# MPU6050.net
KiCad netlist of a schematic drawn in Altium Designer
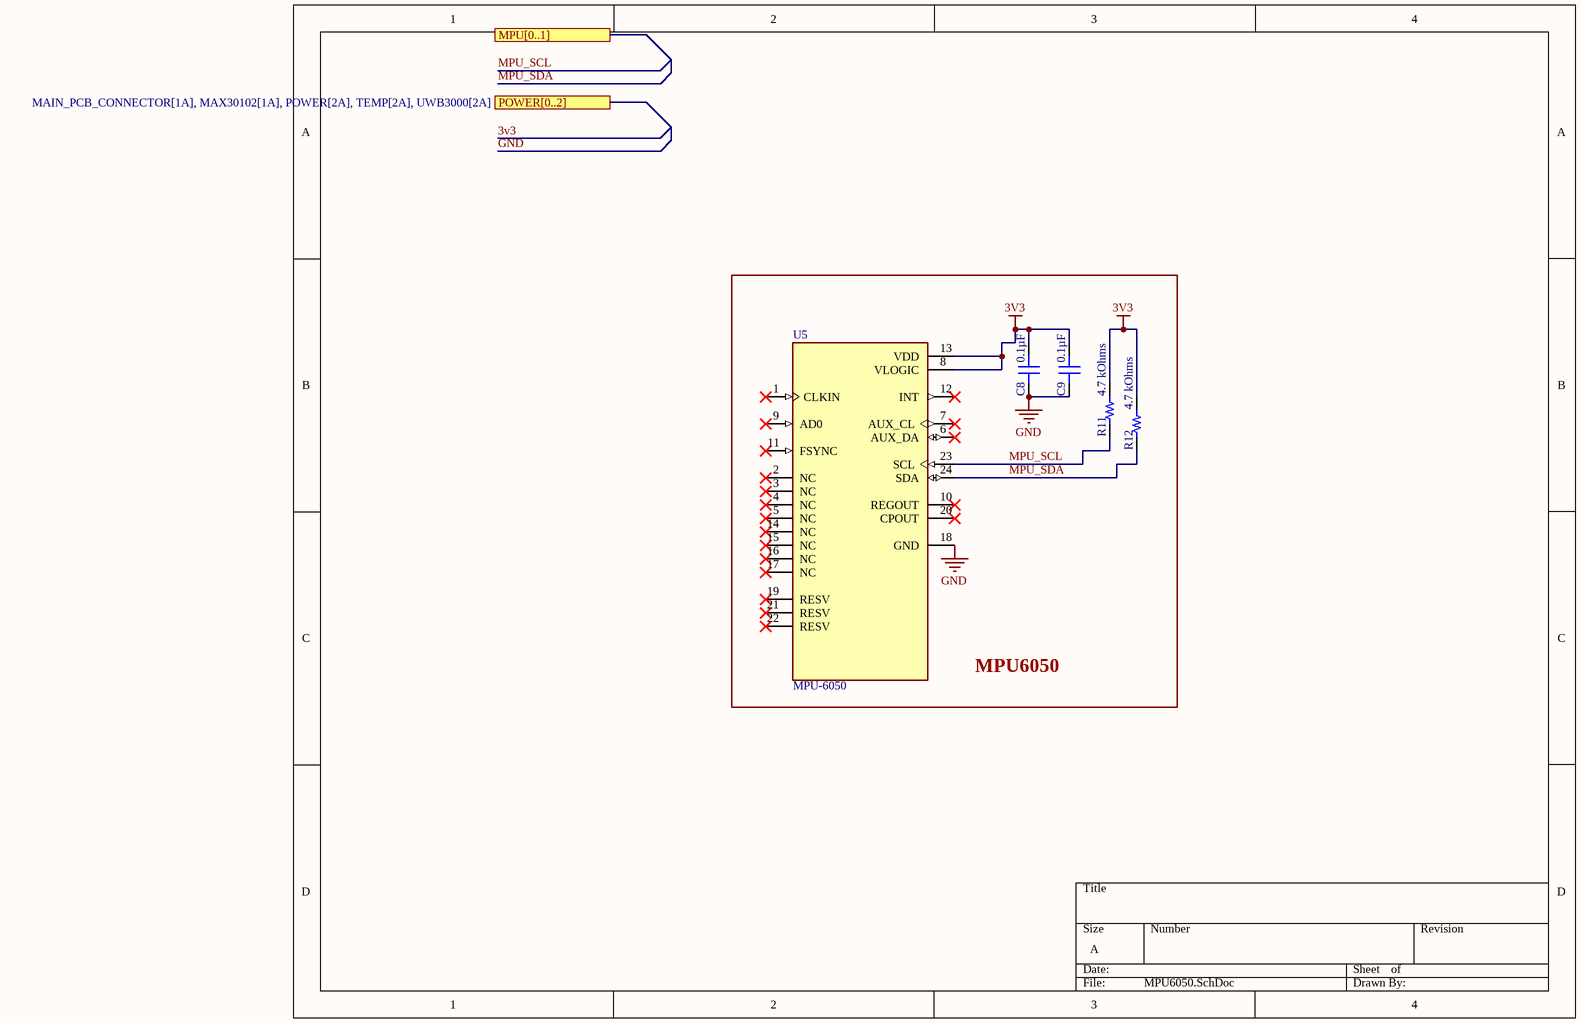
[diagram p0: MPU6050.SchDoc]

(export (version "E")
  (design (tool "Eeschema 10.0.6"))
  (components
    (comp (ref "C8")
      (value "0.1µF")
      (footprint "CAP 0402_1005")
      (description "CAP CER 0.1UF 10V Y5V 0402")
      (fields
        (field (name "MP") "0402ZG104ZAT2A")
        (field (name "CAPACITANCE") "0.1µF")
        (field (name "MF") "AVX Corporation")
      )
      (libsource (lib "Celestial Altium Library - altium_library") (part "Capacitor"))
    )
    (comp (ref "C9")
      (value "0.1µF")
      (footprint "CAP 0402_1005")
      (description "CAP CER 0.1UF 10V Y5V 0402")
      (fields
        (field (name "MP") "0402ZG104ZAT2A")
        (field (name "CAPACITANCE") "0.1µF")
        (field (name "MF") "AVX Corporation")
      )
      (libsource (lib "Celestial Altium Library - altium_library") (part "Capacitor"))
    )
    (comp (ref "R11")
      (value "4.7 kOhms")
      (footprint "YAGEO RES 0402_1005")
      (description "RES SMD 4.7K OHM 1% 1/16W 0402")
      (fields (field (name "MP") "RT0402FRE074K7L") (field (name "MF") "Yageo"))
      (libsource (lib "Celestial Altium Library - altium_library") (part "Resistor"))
    )
    (comp (ref "R12")
      (value "4.7 kOhms")
      (footprint "YAGEO RES 0402_1005")
      (description "RES SMD 4.7K OHM 1% 1/16W 0402")
      (fields (field (name "MP") "RT0402FRE074K7L") (field (name "MF") "Yageo"))
      (libsource (lib "Celestial Altium Library - altium_library") (part "Resistor"))
    )
    (comp (ref "U5")
      (value "MPU-6050")
      (footprint "QFN50P400X400X95-24N")
      (description "MPU-6050 series Accelerometer, Gyroscope, 3 Axis Sensor Evaluation Board")
      (fields (field (name "MF") "TDK InvenSense"))
      (libsource (lib "MPU-6050") (part "MPU-6050"))
    )
  )
  (nets
    (net (code "8") (name "/MPU_SCL") (class "Default")
      (node (ref "R11") (pin "1") (pinfunction "1_1") (pintype "passive"))
      (node (ref "U5") (pin "23") (pinfunction "SCL_23") (pintype "input"))
    )
    (net (code "9") (name "/MPU_SDA") (class "Default")
      (node (ref "R12") (pin "1") (pinfunction "1_1") (pintype "passive"))
      (node (ref "U5") (pin "24") (pinfunction "SDA_24") (pintype "bidirectional"))
    )
    (net (code "11") (name "3V3") (class "Default")
      (node (ref "C8") (pin "2") (pinfunction "2_2") (pintype "passive"))
      (node (ref "C9") (pin "2") (pinfunction "2_2") (pintype "passive"))
      (node (ref "R11") (pin "2") (pinfunction "2_2") (pintype "passive"))
      (node (ref "R12") (pin "2") (pinfunction "2_2") (pintype "passive"))
      (node (ref "U5") (pin "13") (pinfunction "VDD_13") (pintype "power_in"))
      (node (ref "U5") (pin "8") (pinfunction "VLOGIC_8") (pintype "power_in"))
    )
    (net (code "12") (name "GND") (class "Default")
      (node (ref "C8") (pin "1") (pinfunction "1_1") (pintype "passive"))
      (node (ref "C9") (pin "1") (pinfunction "1_1") (pintype "passive"))
      (node (ref "U5") (pin "18") (pinfunction "GND_18") (pintype "power_in"))
    )
    (net (code "13") (name "unconnected-(U5-AD0-Pad9)") (class "Default")
      (node (ref "U5") (pin "9") (pinfunction "AD0_9") (pintype "input+no_connect"))
    )
    (net (code "14") (name "unconnected-(U5-AUX_CL-Pad7)") (class "Default")
      (node (ref "U5") (pin "7") (pinfunction "AUX_CL_7") (pintype "output+no_connect"))
    )
    (net (code "15") (name "unconnected-(U5-AUX_DA-Pad6)") (class "Default")
      (node (ref "U5") (pin "6") (pinfunction "AUX_DA_6") (pintype "bidirectional+no_connect"))
    )
    (net (code "16") (name "unconnected-(U5-CLKIN-Pad1)") (class "Default")
      (node (ref "U5") (pin "1") (pinfunction "CLKIN_1") (pintype "input+no_connect"))
    )
    (net (code "17") (name "unconnected-(U5-CPOUT-Pad20)") (class "Default")
      (node (ref "U5") (pin "20") (pinfunction "CPOUT_20") (pintype "passive+no_connect"))
    )
    (net (code "18") (name "unconnected-(U5-FSYNC-Pad11)") (class "Default")
      (node (ref "U5") (pin "11") (pinfunction "FSYNC_11") (pintype "input+no_connect"))
    )
    (net (code "19") (name "unconnected-(U5-INT-Pad12)") (class "Default")
      (node (ref "U5") (pin "12") (pinfunction "INT_12") (pintype "output+no_connect"))
    )
    (net (code "20") (name "unconnected-(U5-NC-Pad2)") (class "Default")
      (node (ref "U5") (pin "2") (pinfunction "NC_2") (pintype "passive+no_connect"))
    )
    (net (code "21") (name "unconnected-(U5-NC-Pad3)") (class "Default")
      (node (ref "U5") (pin "3") (pinfunction "NC_3") (pintype "passive+no_connect"))
    )
    (net (code "22") (name "unconnected-(U5-NC-Pad4)") (class "Default")
      (node (ref "U5") (pin "4") (pinfunction "NC_4") (pintype "passive+no_connect"))
    )
    (net (code "23") (name "unconnected-(U5-NC-Pad5)") (class "Default")
      (node (ref "U5") (pin "5") (pinfunction "NC_5") (pintype "passive+no_connect"))
    )
    (net (code "24") (name "unconnected-(U5-NC-Pad14)") (class "Default")
      (node (ref "U5") (pin "14") (pinfunction "NC_14") (pintype "passive+no_connect"))
    )
    (net (code "25") (name "unconnected-(U5-NC-Pad15)") (class "Default")
      (node (ref "U5") (pin "15") (pinfunction "NC_15") (pintype "passive+no_connect"))
    )
    (net (code "26") (name "unconnected-(U5-NC-Pad16)") (class "Default")
      (node (ref "U5") (pin "16") (pinfunction "NC_16") (pintype "passive+no_connect"))
    )
    (net (code "27") (name "unconnected-(U5-NC-Pad17)") (class "Default")
      (node (ref "U5") (pin "17") (pinfunction "NC_17") (pintype "passive+no_connect"))
    )
    (net (code "28") (name "unconnected-(U5-REGOUT-Pad10)") (class "Default")
      (node (ref "U5") (pin "10") (pinfunction "REGOUT_10") (pintype "passive+no_connect"))
    )
    (net (code "29") (name "unconnected-(U5-RESV-Pad19)") (class "Default")
      (node (ref "U5") (pin "19") (pinfunction "RESV_19") (pintype "passive+no_connect"))
    )
    (net (code "30") (name "unconnected-(U5-RESV-Pad21)") (class "Default")
      (node (ref "U5") (pin "21") (pinfunction "RESV_21") (pintype "passive+no_connect"))
    )
    (net (code "31") (name "unconnected-(U5-RESV-Pad22)") (class "Default")
      (node (ref "U5") (pin "22") (pinfunction "RESV_22") (pintype "passive+no_connect"))
    )
  )
)
